# DAC_MIC.net
KiCad netlist of a schematic drawn in Altium Designer
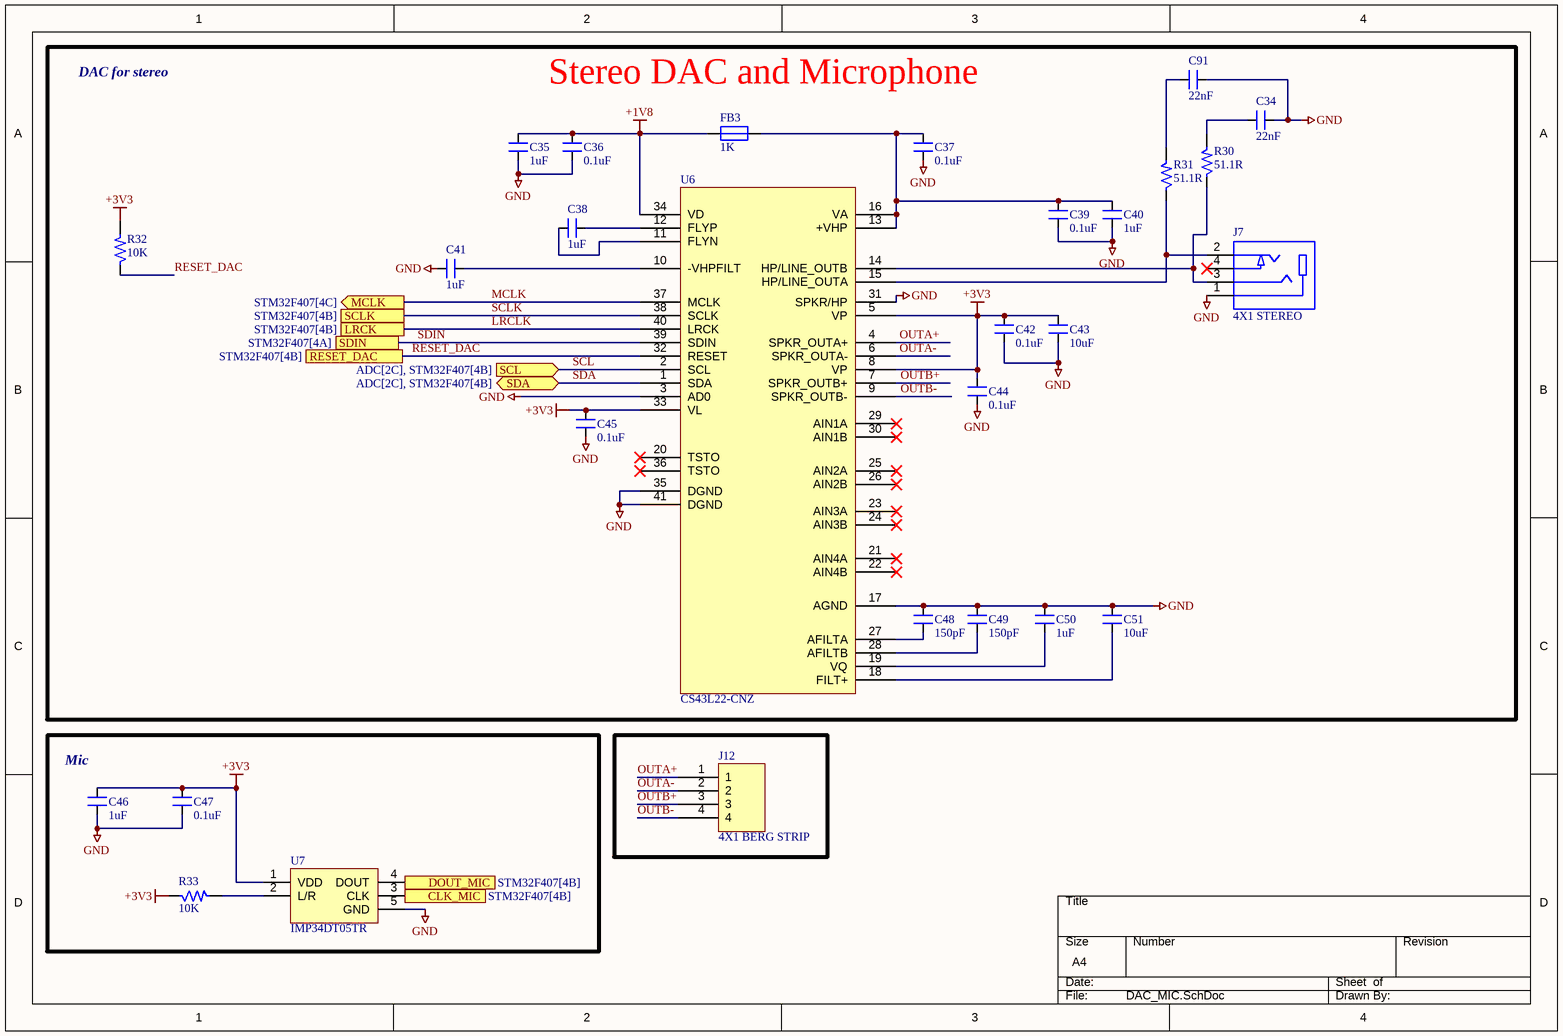
[diagram p0: DAC_MIC.SchDoc]

(export (version "E")
  (design (tool "Eeschema 10.0.6"))
  (components
    (comp (ref "C34")
      (value "22nF")
      (footprint "CAP_0805")
      (description "0.022µF ±10% 50V Ceramic Capacitor X7R 0805 (2012 Metric)")
      (fields
        (field (name "MANUFACTURER") "Samsung Electro-Mechanics")
        (field (name "MANUFACTURER PART NUMBER") "CL21B223KBANNNC")
      )
      (libsource (lib "ESTEEMPCBLIB") (part "CAP_22nF-50V-10%-0805"))
    )
    (comp (ref "C35")
      (value "1uF")
      (footprint "CAP_0805")
      (description "1µF ±5% 50V Ceramic Capacitor X7R 0805 (2012 Metric)")
      (fields
        (field (name "MANUFACTURER") "Samsung")
        (field (name "MANUFACTURER PART NUMBER") "CC0805JKX7R9BB105")
      )
      (libsource (lib "ESTEEMPCBLIB") (part "CAP_1uF-50V-5%-0805"))
    )
    (comp (ref "C36")
      (value "0.1uF")
      (footprint "CAP_0805")
      (description "0.1µF ±5% 50V Ceramic Capacitor X7R 0805 (2012 Metric)")
      (fields
        (field (name "MANUFACTURER") "AVX Corporation")
        (field (name "MANUFACTURER PART NUMBER") "08055C104JAT4A")
      )
      (libsource (lib "ESTEEMPCBLIB") (part "CAP_0.1uF-50V-5%-0805"))
    )
    (comp (ref "C37")
      (value "0.1uF")
      (footprint "CAP_0805")
      (description "0.1µF ±5% 50V Ceramic Capacitor X7R 0805 (2012 Metric)")
      (fields
        (field (name "MANUFACTURER") "AVX Corporation")
        (field (name "MANUFACTURER PART NUMBER") "08055C104JAT4A")
      )
      (libsource (lib "ESTEEMPCBLIB") (part "CAP_0.1uF-50V-5%-0805"))
    )
    (comp (ref "C38")
      (value "1uF")
      (footprint "CAP_0805")
      (description "1µF ±5% 50V Ceramic Capacitor X7R 0805 (2012 Metric)")
      (fields
        (field (name "MANUFACTURER") "Samsung")
        (field (name "MANUFACTURER PART NUMBER") "CC0805JKX7R9BB105")
      )
      (libsource (lib "ESTEEMPCBLIB") (part "CAP_1uF-50V-5%-0805"))
    )
    (comp (ref "C39")
      (value "0.1uF")
      (footprint "CAP_0805")
      (description "0.1µF ±5% 50V Ceramic Capacitor X7R 0805 (2012 Metric)")
      (fields
        (field (name "MANUFACTURER") "AVX Corporation")
        (field (name "MANUFACTURER PART NUMBER") "08055C104JAT4A")
      )
      (libsource (lib "ESTEEMPCBLIB") (part "CAP_0.1uF-50V-5%-0805"))
    )
    (comp (ref "C40")
      (value "1uF")
      (footprint "CAP_0805")
      (description "1µF ±5% 50V Ceramic Capacitor X7R 0805 (2012 Metric)")
      (fields
        (field (name "MANUFACTURER") "Samsung")
        (field (name "MANUFACTURER PART NUMBER") "CC0805JKX7R9BB105")
      )
      (libsource (lib "ESTEEMPCBLIB") (part "CAP_1uF-50V-5%-0805"))
    )
    (comp (ref "C41")
      (value "1uF")
      (footprint "CAP_0805")
      (description "1µF ±5% 50V Ceramic Capacitor X7R 0805 (2012 Metric)")
      (fields
        (field (name "MANUFACTURER") "Samsung")
        (field (name "MANUFACTURER PART NUMBER") "CC0805JKX7R9BB105")
      )
      (libsource (lib "ESTEEMPCBLIB") (part "CAP_1uF-50V-5%-0805"))
    )
    (comp (ref "C42")
      (value "0.1uF")
      (footprint "CAP_0805")
      (description "0.1µF ±5% 50V Ceramic Capacitor X7R 0805 (2012 Metric)")
      (fields
        (field (name "MANUFACTURER") "AVX Corporation")
        (field (name "MANUFACTURER PART NUMBER") "08055C104JAT4A")
      )
      (libsource (lib "ESTEEMPCBLIB") (part "CAP_0.1uF-50V-5%-0805"))
    )
    (comp (ref "C43")
      (value "10uF")
      (footprint "CAP_1206")
      (description "10µF ±10% 50V Ceramic Capacitor X7R 1206 (3216 Metric)")
      (fields
        (field (name "MANUFACTURER") "KEMET")
        (field (name "MANUFACTURER PART NUMBER") "CL31B106KBHNNNE")
      )
      (libsource (lib "ESTEEMPCBLIB") (part "CAP_10uF-50V-10%-1206"))
    )
    (comp (ref "C44")
      (value "0.1uF")
      (footprint "CAP_0805")
      (description "0.1µF ±5% 50V Ceramic Capacitor X7R 0805 (2012 Metric)")
      (fields
        (field (name "MANUFACTURER") "AVX Corporation")
        (field (name "MANUFACTURER PART NUMBER") "08055C104JAT4A")
      )
      (libsource (lib "ESTEEMPCBLIB") (part "CAP_0.1uF-50V-5%-0805"))
    )
    (comp (ref "C45")
      (value "0.1uF")
      (footprint "CAP_0805")
      (description "0.1µF ±5% 50V Ceramic Capacitor X7R 0805 (2012 Metric)")
      (fields
        (field (name "MANUFACTURER") "AVX Corporation")
        (field (name "MANUFACTURER PART NUMBER") "08055C104JAT4A")
      )
      (libsource (lib "ESTEEMPCBLIB") (part "CAP_0.1uF-50V-5%-0805"))
    )
    (comp (ref "C46")
      (value "1uF")
      (footprint "CAP_0805")
      (description "1µF ±5% 50V Ceramic Capacitor X7R 0805 (2012 Metric)")
      (fields
        (field (name "MANUFACTURER") "Samsung")
        (field (name "MANUFACTURER PART NUMBER") "CC0805JKX7R9BB105")
      )
      (libsource (lib "ESTEEMPCBLIB") (part "CAP_1uF-50V-5%-0805"))
    )
    (comp (ref "C47")
      (value "0.1uF")
      (footprint "CAP_0805")
      (description "0.1µF ±5% 50V Ceramic Capacitor X7R 0805 (2012 Metric)")
      (fields
        (field (name "MANUFACTURER") "AVX Corporation")
        (field (name "MANUFACTURER PART NUMBER") "08055C104JAT4A")
      )
      (libsource (lib "ESTEEMPCBLIB") (part "CAP_0.1uF-50V-5%-0805"))
    )
    (comp (ref "C48")
      (value "150pF")
      (footprint "CAP_0805")
      (description "150pF ±10% 50V Ceramic Capacitor C0G, NP0 0805 (2012 Metric)")
      (fields
        (field (name "MANUFACTURER") "AVX Corporation")
        (field (name "MANUFACTURER PART NUMBER") "08055A151KAT2A")
      )
      (libsource (lib "ESTEEMPCBLIB") (part "CAP_150pF-50V-10%-0805"))
    )
    (comp (ref "C49")
      (value "150pF")
      (footprint "CAP_0805")
      (description "150pF ±10% 50V Ceramic Capacitor C0G, NP0 0805 (2012 Metric)")
      (fields
        (field (name "MANUFACTURER") "AVX Corporation")
        (field (name "MANUFACTURER PART NUMBER") "08055A151KAT2A")
      )
      (libsource (lib "ESTEEMPCBLIB") (part "CAP_150pF-50V-10%-0805"))
    )
    (comp (ref "C50")
      (value "1uF")
      (footprint "CAP_0805")
      (description "1µF ±5% 50V Ceramic Capacitor X7R 0805 (2012 Metric)")
      (fields
        (field (name "MANUFACTURER") "Samsung")
        (field (name "MANUFACTURER PART NUMBER") "CC0805JKX7R9BB105")
      )
      (libsource (lib "ESTEEMPCBLIB") (part "CAP_1uF-50V-5%-0805"))
    )
    (comp (ref "C51")
      (value "10uF")
      (footprint "CAP_1206")
      (description "10µF ±10% 50V Ceramic Capacitor X7R 1206 (3216 Metric)")
      (fields
        (field (name "MANUFACTURER") "KEMET")
        (field (name "MANUFACTURER PART NUMBER") "CL31B106KBHNNNE")
      )
      (libsource (lib "ESTEEMPCBLIB") (part "CAP_10uF-50V-10%-1206"))
    )
    (comp (ref "C91")
      (value "22nF")
      (footprint "CAP_0805")
      (description "0.022µF ±10% 50V Ceramic Capacitor X7R 0805 (2012 Metric)")
      (fields
        (field (name "MANUFACTURER") "Samsung Electro-Mechanics")
        (field (name "MANUFACTURER PART NUMBER") "CL21B223KBANNNC")
      )
      (libsource (lib "ESTEEMPCBLIB") (part "CAP_22nF-50V-10%-0805"))
    )
    (comp (ref "FB3")
      (value "1K")
      (footprint "IND_0805")
      (description "1 kOhms @ 100MHz 1 Power Line Ferrite Bead 0805 (2012 Metric) 1.6A")
      (fields
        (field (name "MANUFACTURER") "Laird")
        (field (name "MANUFACTURER PART NUMBER") "BLM21SP102SH1D")
      )
      (libsource (lib "ESTEEMPCBLIB") (part "FB_1K-100MHZ-1.6A-0805"))
    )
    (comp (ref "J7")
      (value "4X1 STEREO")
      (footprint "CON_SJ-2504A-SMT-TR_SMD")
      (fields
        (field (name "MANUFACTURER") "CUI Devices")
        (field (name "MANUFACTURER PART NUMBER") "SJ-2504A-SMT-TR")
      )
      (libsource (lib "ESTEEMPCBLIB") (part "CON-PLG-STEREO_4X1-100-RA-SMD"))
    )
    (comp (ref "J12")
      (value "4X1 BERG STRIP")
      (footprint "CON4_100_40D72_TH_ST_MALE")
      (description "4 Pins, 1 Row 2.54mm Pitch, Straight bergstrip, Male")
      (fields (field (name "MANUFACTURER") "NA"))
      (libsource (lib "ESTEEMPCBLIB") (part "CON-BS-PLG_4X1-100-ST-TH"))
    )
    (comp (ref "R30")
      (value "51.1R")
      (footprint "RES_0603")
      (description "51.1 Ohms ±1% 0.1W, 1/10W Chip Resistor 0603 (1608 Metric) Thick Film")
      (fields
        (field (name "MANUFACTURER") "Vishay Dale")
        (field (name "MANUFACTURER PART NUMBER") "CRCW060351R1FKEAC")
      )
      (libsource (lib "ESTEEMPCBLIB") (part "RES_51.1R-0.1W-1%-0603"))
    )
    (comp (ref "R31")
      (value "51.1R")
      (footprint "RES_0603")
      (description "51.1 Ohms ±1% 0.1W, 1/10W Chip Resistor 0603 (1608 Metric) Thick Film")
      (fields
        (field (name "MANUFACTURER") "Vishay Dale")
        (field (name "MANUFACTURER PART NUMBER") "CRCW060351R1FKEAC")
      )
      (libsource (lib "ESTEEMPCBLIB") (part "RES_51.1R-0.1W-1%-0603"))
    )
    (comp (ref "R32")
      (value "10K")
      (footprint "RES_0603")
      (description "10 kOhms ±1% 0.1W, 1/10W Chip Resistor 0603 (1608 Metric) Automotive AEC-Q200 Thick Film")
      (fields (field (name "MANUFACTURER") "Walsin") (field (name "MANUFACTURER PART NUMBER") "WR06X1002FTL"))
      (libsource (lib "ESTEEMPCBLIB") (part "RES_10K-0.1W-1%-0603"))
    )
    (comp (ref "R33")
      (value "10K")
      (footprint "RES_0603")
      (description "10 kOhms ±1% 0.1W, 1/10W Chip Resistor 0603 (1608 Metric) Automotive AEC-Q200 Thick Film")
      (fields (field (name "MANUFACTURER") "Walsin") (field (name "MANUFACTURER PART NUMBER") "WR06X1002FTL"))
      (libsource (lib "ESTEEMPCBLIB") (part "RES_10K-0.1W-1%-0603"))
    )
    (comp (ref "U6")
      (value "CS43L22-CNZ")
      (footprint "QFN40_19_284_33X9_SMD")
      (description "Audio D/A Converter ICs Low Power Stereo DAC w/ClassD Spkr Driver")
      (fields (field (name "MANUFACTURER") "Cirrus Logic"))
      (libsource (lib "ESTEEMPCBLIB") (part "IC_CS43L22"))
    )
    (comp (ref "U7")
      (value "IMP34DT05TR")
      (footprint "HCLGA-4_53_137_15X37_SMD")
      (description "MEMS Microphones AUTO & INDUSTRIAL SENSORS")
      (fields (field (name "MANUFACTURER") "STMicroelectronics"))
      (libsource (lib "ESTEEMPCBLIB") (part "IC_IMP34DT05TR"))
    )
  )
  (nets
    (net (code "1") (name "+1V8") (class "Default")
      (node (ref "C35") (pin "2") (pinfunction "2_2") (pintype "passive"))
      (node (ref "C36") (pin "2") (pinfunction "2_2") (pintype "passive"))
      (node (ref "FB3") (pin "1") (pinfunction "1_1") (pintype "passive"))
      (node (ref "U6") (pin "34") (pinfunction "VD_34") (pintype "passive"))
    )
    (net (code "2") (name "+3V3") (class "Default")
      (node (ref "C42") (pin "2") (pinfunction "2_2") (pintype "passive"))
      (node (ref "C43") (pin "2") (pinfunction "2_2") (pintype "passive"))
      (node (ref "C44") (pin "2") (pinfunction "2_2") (pintype "passive"))
      (node (ref "C45") (pin "2") (pinfunction "2_2") (pintype "passive"))
      (node (ref "C46") (pin "1") (pinfunction "1_1") (pintype "passive"))
      (node (ref "C47") (pin "2") (pinfunction "2_2") (pintype "passive"))
      (node (ref "R32") (pin "2") (pinfunction "2_2") (pintype "passive"))
      (node (ref "R33") (pin "1") (pinfunction "1_1") (pintype "passive"))
      (node (ref "U6") (pin "33") (pinfunction "VL_33") (pintype "passive"))
      (node (ref "U6") (pin "5") (pinfunction "VP_5") (pintype "passive"))
      (node (ref "U6") (pin "8") (pinfunction "VP_8") (pintype "passive"))
      (node (ref "U7") (pin "1") (pinfunction "VDD_1") (pintype "passive"))
    )
    (net (code "3") (name "/CLK_MIC") (class "Default")
      (node (ref "U7") (pin "3") (pinfunction "CLK_3") (pintype "passive"))
    )
    (net (code "4") (name "/DOUT_MIC") (class "Default")
      (node (ref "U7") (pin "4") (pinfunction "DOUT_4") (pintype "passive"))
    )
    (net (code "5") (name "/LRCLK") (class "Default")
      (node (ref "U6") (pin "40") (pinfunction "LRCK_40") (pintype "passive"))
    )
    (net (code "6") (name "/MCLK") (class "Default")
      (node (ref "U6") (pin "37") (pinfunction "MCLK_37") (pintype "passive"))
    )
    (net (code "7") (name "/OUTA+") (class "Default")
      (node (ref "J12") (pin "1") (pinfunction "1_1") (pintype "passive"))
      (node (ref "U6") (pin "4") (pinfunction "SPKR_OUTA+_4") (pintype "passive"))
    )
    (net (code "8") (name "/OUTA-") (class "Default")
      (node (ref "J12") (pin "2") (pinfunction "2_2") (pintype "passive"))
      (node (ref "U6") (pin "6") (pinfunction "SPKR_OUTA-_6") (pintype "passive"))
    )
    (net (code "9") (name "/OUTB+") (class "Default")
      (node (ref "J12") (pin "3") (pinfunction "3_3") (pintype "passive"))
      (node (ref "U6") (pin "7") (pinfunction "SPKR_OUTB+_7") (pintype "passive"))
    )
    (net (code "10") (name "/OUTB-") (class "Default")
      (node (ref "J12") (pin "4") (pinfunction "4_4") (pintype "passive"))
      (node (ref "U6") (pin "9") (pinfunction "SPKR_OUTB-_9") (pintype "passive"))
    )
    (net (code "11") (name "/RESET_DAC") (class "Default")
      (node (ref "R32") (pin "1") (pinfunction "1_1") (pintype "passive"))
      (node (ref "U6") (pin "32") (pinfunction "RESET_32") (pintype "passive"))
    )
    (net (code "12") (name "/SCL") (class "Default")
      (node (ref "U6") (pin "2") (pinfunction "SCL_2") (pintype "passive"))
    )
    (net (code "13") (name "/SCLK") (class "Default")
      (node (ref "U6") (pin "38") (pinfunction "SCLK_38") (pintype "passive"))
    )
    (net (code "14") (name "/SDA") (class "Default")
      (node (ref "U6") (pin "1") (pinfunction "SDA_1") (pintype "passive"))
    )
    (net (code "15") (name "/SDIN") (class "Default")
      (node (ref "U6") (pin "39") (pinfunction "SDIN_39") (pintype "passive"))
    )
    (net (code "16") (name "GND") (class "Default")
      (node (ref "C34") (pin "2") (pinfunction "2_2") (pintype "passive"))
      (node (ref "C35") (pin "1") (pinfunction "1_1") (pintype "passive"))
      (node (ref "C36") (pin "1") (pinfunction "1_1") (pintype "passive"))
      (node (ref "C37") (pin "1") (pinfunction "1_1") (pintype "passive"))
      (node (ref "C39") (pin "1") (pinfunction "1_1") (pintype "passive"))
      (node (ref "C40") (pin "2") (pinfunction "2_2") (pintype "passive"))
      (node (ref "C41") (pin "1") (pinfunction "1_1") (pintype "passive"))
      (node (ref "C42") (pin "1") (pinfunction "1_1") (pintype "passive"))
      (node (ref "C43") (pin "1") (pinfunction "1_1") (pintype "passive"))
      (node (ref "C44") (pin "1") (pinfunction "1_1") (pintype "passive"))
      (node (ref "C45") (pin "1") (pinfunction "1_1") (pintype "passive"))
      (node (ref "C46") (pin "2") (pinfunction "2_2") (pintype "passive"))
      (node (ref "C47") (pin "1") (pinfunction "1_1") (pintype "passive"))
      (node (ref "C48") (pin "2") (pinfunction "2_2") (pintype "passive"))
      (node (ref "C49") (pin "2") (pinfunction "2_2") (pintype "passive"))
      (node (ref "C50") (pin "2") (pinfunction "2_2") (pintype "passive"))
      (node (ref "C51") (pin "2") (pinfunction "2_2") (pintype "passive"))
      (node (ref "C91") (pin "2") (pinfunction "2_2") (pintype "passive"))
      (node (ref "J7") (pin "1") (pinfunction "1_1") (pintype "passive"))
      (node (ref "U6") (pin "17") (pinfunction "AGND_17") (pintype "passive"))
      (node (ref "U6") (pin "3") (pinfunction "AD0_3") (pintype "passive"))
      (node (ref "U6") (pin "31") (pinfunction "SPKR/HP_31") (pintype "passive"))
      (node (ref "U6") (pin "35") (pinfunction "DGND_35") (pintype "passive"))
      (node (ref "U6") (pin "41") (pinfunction "DGND_41") (pintype "passive"))
      (node (ref "U7") (pin "5") (pinfunction "GND_5") (pintype "passive"))
    )
    (net (code "17") (name "Net-(C34-Pad1)") (class "Default")
      (node (ref "C34") (pin "1") (pinfunction "1_1") (pintype "passive"))
      (node (ref "R30") (pin "2") (pinfunction "2_2") (pintype "passive"))
    )
    (net (code "18") (name "Net-(C91-Pad1)") (class "Default")
      (node (ref "C91") (pin "1") (pinfunction "1_1") (pintype "passive"))
      (node (ref "R31") (pin "2") (pinfunction "2_2") (pintype "passive"))
    )
    (net (code "19") (name "Net-(U6-+VHP)") (class "Default")
      (node (ref "C37") (pin "2") (pinfunction "2_2") (pintype "passive"))
      (node (ref "C39") (pin "2") (pinfunction "2_2") (pintype "passive"))
      (node (ref "C40") (pin "1") (pinfunction "1_1") (pintype "passive"))
      (node (ref "FB3") (pin "2") (pinfunction "2_2") (pintype "passive"))
      (node (ref "U6") (pin "13") (pinfunction "+VHP_13") (pintype "passive"))
      (node (ref "U6") (pin "16") (pinfunction "VA_16") (pintype "passive"))
    )
    (net (code "20") (name "Net-(U6--VHPFILT)") (class "Default")
      (node (ref "C41") (pin "2") (pinfunction "2_2") (pintype "passive"))
      (node (ref "U6") (pin "10") (pinfunction "-VHPFILT_10") (pintype "passive"))
    )
    (net (code "21") (name "Net-(U6-AFILTA)") (class "Default")
      (node (ref "C48") (pin "1") (pinfunction "1_1") (pintype "passive"))
      (node (ref "U6") (pin "27") (pinfunction "AFILTA_27") (pintype "passive"))
    )
    (net (code "22") (name "Net-(U6-AFILTB)") (class "Default")
      (node (ref "C49") (pin "1") (pinfunction "1_1") (pintype "passive"))
      (node (ref "U6") (pin "28") (pinfunction "AFILTB_28") (pintype "passive"))
    )
    (net (code "23") (name "Net-(U6-FILT+)") (class "Default")
      (node (ref "C51") (pin "1") (pinfunction "1_1") (pintype "passive"))
      (node (ref "U6") (pin "18") (pinfunction "FILT+_18") (pintype "passive"))
    )
    (net (code "24") (name "Net-(U6-FLYN)") (class "Default")
      (node (ref "C38") (pin "2") (pinfunction "2_2") (pintype "passive"))
      (node (ref "U6") (pin "11") (pinfunction "FLYN_11") (pintype "passive"))
    )
    (net (code "25") (name "Net-(U6-FLYP)") (class "Default")
      (node (ref "C38") (pin "1") (pinfunction "1_1") (pintype "passive"))
      (node (ref "U6") (pin "12") (pinfunction "FLYP_12") (pintype "passive"))
    )
    (net (code "26") (name "Net-(U6-HP{slash}LINE_OUTA)") (class "Default")
      (node (ref "J7") (pin "2") (pinfunction "2_2") (pintype "passive"))
      (node (ref "R31") (pin "1") (pinfunction "1_1") (pintype "passive"))
      (node (ref "U6") (pin "15") (pinfunction "HP/LINE_OUTA_15") (pintype "passive"))
    )
    (net (code "27") (name "Net-(U6-HP{slash}LINE_OUTB)") (class "Default")
      (node (ref "J7") (pin "3") (pinfunction "3_3") (pintype "passive"))
      (node (ref "R30") (pin "1") (pinfunction "1_1") (pintype "passive"))
      (node (ref "U6") (pin "14") (pinfunction "HP/LINE_OUTB_14") (pintype "passive"))
    )
    (net (code "28") (name "Net-(U6-VQ)") (class "Default")
      (node (ref "C50") (pin "1") (pinfunction "1_1") (pintype "passive"))
      (node (ref "U6") (pin "19") (pinfunction "VQ_19") (pintype "passive"))
    )
    (net (code "29") (name "Net-(U7-L{slash}R)") (class "Default")
      (node (ref "R33") (pin "2") (pinfunction "2_2") (pintype "passive"))
      (node (ref "U7") (pin "2") (pinfunction "L/R_2") (pintype "passive"))
    )
    (net (code "30") (name "unconnected-(J7-Pad4)") (class "Default")
      (node (ref "J7") (pin "4") (pinfunction "4_4") (pintype "passive+no_connect"))
    )
    (net (code "31") (name "unconnected-(U6-AIN1A-Pad29)") (class "Default")
      (node (ref "U6") (pin "29") (pinfunction "AIN1A_29") (pintype "passive+no_connect"))
    )
    (net (code "32") (name "unconnected-(U6-AIN1B-Pad30)") (class "Default")
      (node (ref "U6") (pin "30") (pinfunction "AIN1B_30") (pintype "passive+no_connect"))
    )
    (net (code "33") (name "unconnected-(U6-AIN2A-Pad25)") (class "Default")
      (node (ref "U6") (pin "25") (pinfunction "AIN2A_25") (pintype "passive+no_connect"))
    )
    (net (code "34") (name "unconnected-(U6-AIN2B-Pad26)") (class "Default")
      (node (ref "U6") (pin "26") (pinfunction "AIN2B_26") (pintype "passive+no_connect"))
    )
    (net (code "35") (name "unconnected-(U6-AIN3A-Pad23)") (class "Default")
      (node (ref "U6") (pin "23") (pinfunction "AIN3A_23") (pintype "passive+no_connect"))
    )
    (net (code "36") (name "unconnected-(U6-AIN3B-Pad24)") (class "Default")
      (node (ref "U6") (pin "24") (pinfunction "AIN3B_24") (pintype "passive+no_connect"))
    )
    (net (code "37") (name "unconnected-(U6-AIN4A-Pad21)") (class "Default")
      (node (ref "U6") (pin "21") (pinfunction "AIN4A_21") (pintype "passive+no_connect"))
    )
    (net (code "38") (name "unconnected-(U6-AIN4B-Pad22)") (class "Default")
      (node (ref "U6") (pin "22") (pinfunction "AIN4B_22") (pintype "passive+no_connect"))
    )
    (net (code "39") (name "unconnected-(U6-TSTO-Pad20)") (class "Default")
      (node (ref "U6") (pin "20") (pinfunction "TSTO_20") (pintype "passive+no_connect"))
    )
    (net (code "40") (name "unconnected-(U6-TSTO-Pad36)") (class "Default")
      (node (ref "U6") (pin "36") (pinfunction "TSTO_36") (pintype "passive+no_connect"))
    )
  )
)
